# FloppyController.net
KiCad netlist of a schematic drawn in EAGLE
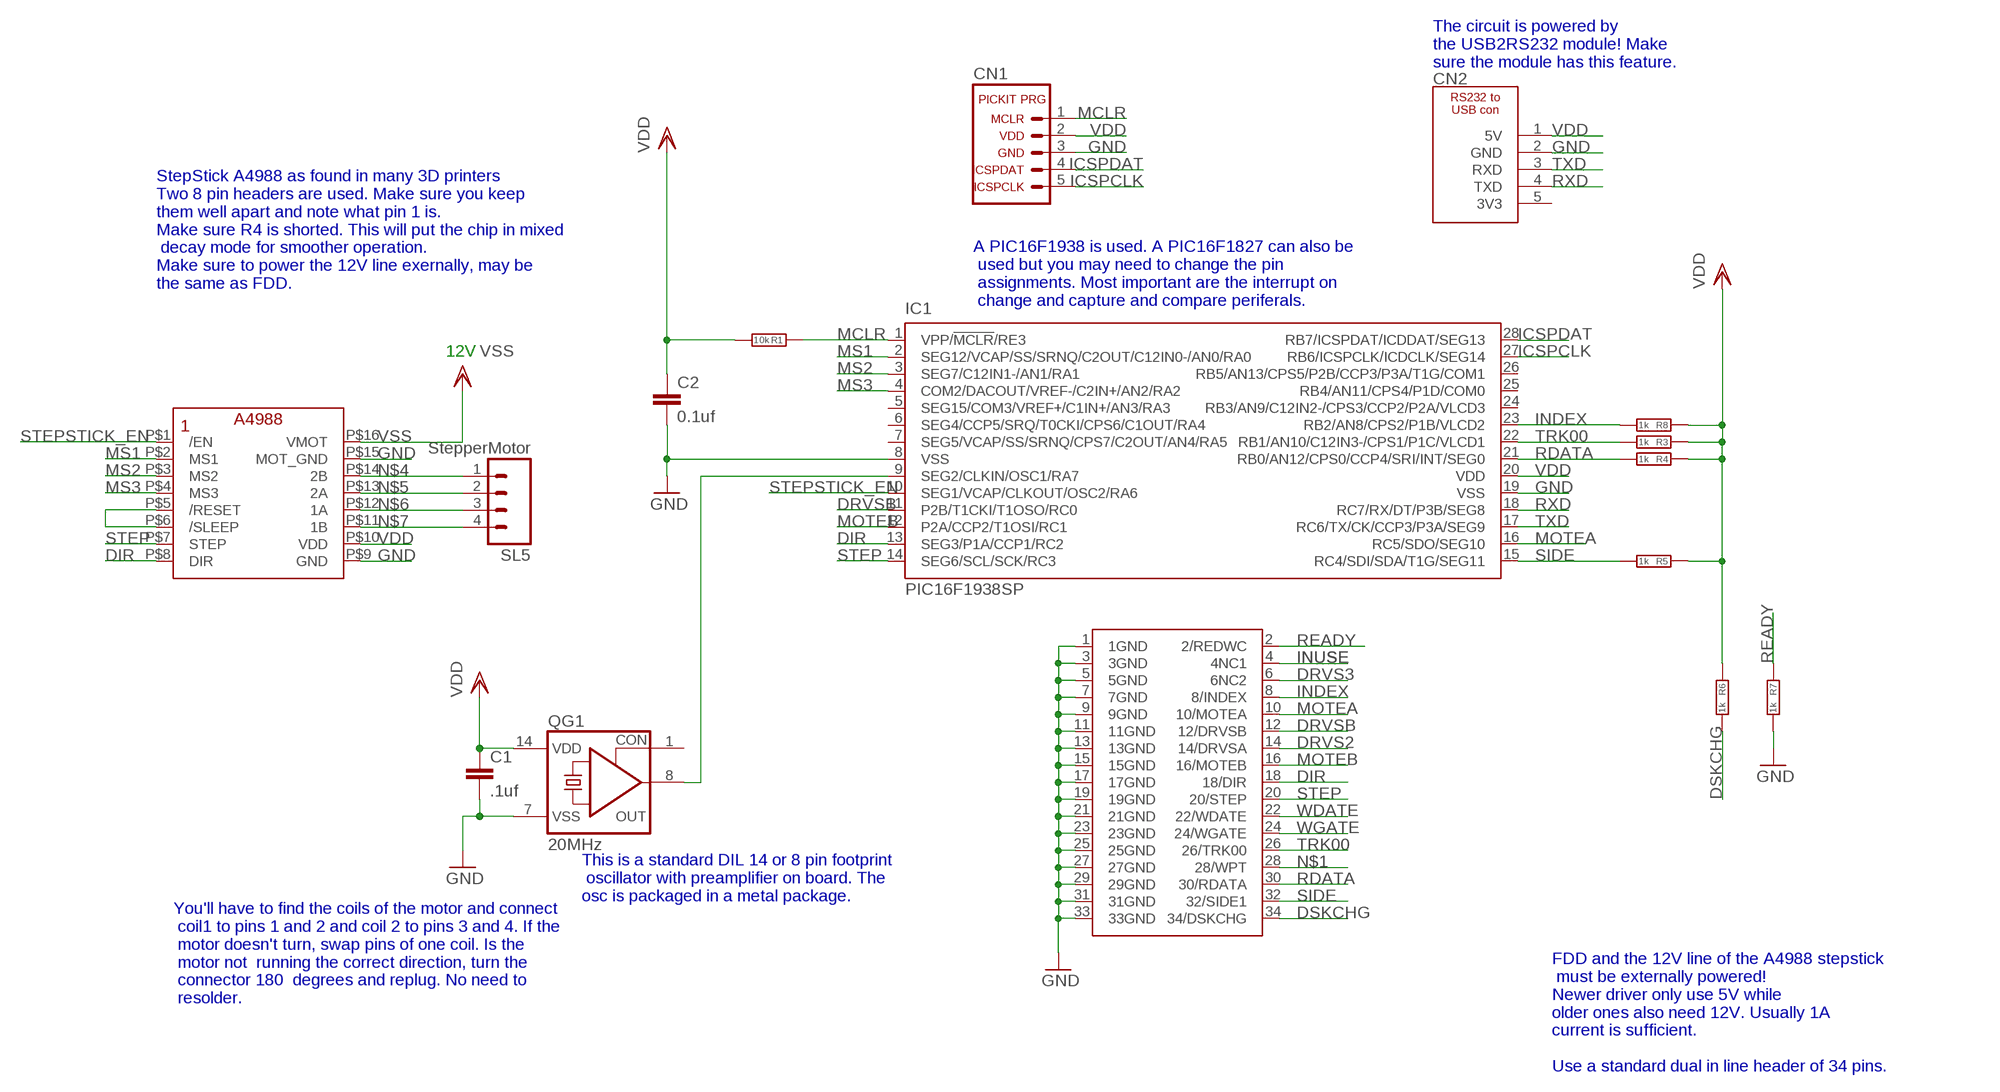
[diagram p0: schematic, sheet 1]

(export (version "E")
  (design (tool "Eeschema 10.0.6"))
  (components
    (comp (ref "C1")
      (value ".1uf")
      (footprint "eagle-import:C5B3")
      (libsource (lib "eagle-import") (part "C5/3"))
    )
    (comp (ref "C2")
      (value "0.1uf")
      (footprint "eagle-import:C5B3")
      (libsource (lib "eagle-import") (part "C5/3"))
    )
    (comp (ref "CN1")
      (value "PICKIT3CONNECTOR")
      (footprint "eagle-import:05P")
      (libsource (lib "eagle-import") (part "PICKIT3CONNECTOR"))
    )
    (comp (ref "CN2")
      (value "RS232_TO_USB_CONNECTOR")
      (footprint "eagle-import:05P")
      (libsource (lib "eagle-import") (part "RS232_TO_USB_CONNECTOR"))
    )
    (comp (ref "IC1")
      (value "PIC16F1938SP")
      (footprint "eagle-import:DIL28-3")
      (fields (field (name "MPN") "PIC16F1938-I/SP"))
      (libsource (lib "eagle-import") (part "PIC16F19SP38"))
    )
    (comp (ref "IC2")
      (value "STEPSTICK_A4988")
      (footprint "eagle-import:STEPSTICK_A4988")
      (libsource (lib "eagle-import") (part "STEPSTICK_A4988"))
    )
    (comp (ref "QG1")
      (value "20MHz")
      (footprint "eagle-import:SG51")
      (libsource (lib "eagle-import") (part "CRYSTAL_RES-SG51"))
    )
    (comp (ref "R1")
      (value "10k")
      (footprint "eagle-import:M1206")
      (libsource (lib "eagle-import") (part "R-EU_M1206"))
    )
    (comp (ref "R3")
      (value "1k")
      (footprint "eagle-import:M1206")
      (libsource (lib "eagle-import") (part "R-EU_M1206"))
    )
    (comp (ref "R4")
      (value "1k")
      (footprint "eagle-import:M1206")
      (libsource (lib "eagle-import") (part "R-EU_M1206"))
    )
    (comp (ref "R5")
      (value "1k")
      (footprint "eagle-import:M1206")
      (libsource (lib "eagle-import") (part "R-EU_M1206"))
    )
    (comp (ref "R6")
      (value "1k")
      (footprint "eagle-import:M1206")
      (libsource (lib "eagle-import") (part "R-EU_M1206"))
    )
    (comp (ref "R7")
      (value "1k")
      (footprint "eagle-import:M1206")
      (libsource (lib "eagle-import") (part "R-EU_M1206"))
    )
    (comp (ref "R8")
      (value "1k")
      (footprint "eagle-import:M1206")
      (libsource (lib "eagle-import") (part "R-EU_M1206"))
    )
    (comp (ref "SL5")
      (value "StepperMotor")
      (footprint "eagle-import:04P")
      (libsource (lib "eagle-import") (part "M04"))
    )
    (comp (ref "U$1")
      (value "FLOPPY_34PIN_CONN")
      (footprint "eagle-import:FLOPPY_34PIN_DUALROW")
      (libsource (lib "eagle-import") (part "FLOPPY_34PIN_CONN"))
    )
  )
  (nets
    (net (code "1") (name "/DIR") (class "Default")
      (node (ref "IC1") (pin "13") (pinfunction "SEG3/P1A/CCP1/RC2_13") (pintype "bidirectional"))
      (node (ref "IC2") (pin "P$8") (pinfunction "DIR_P$8") (pintype "input"))
      (node (ref "U$1") (pin "18") (pinfunction "18/DIR_18") (pintype "input"))
    )
    (net (code "2") (name "/DRVS2") (class "Default")
      (node (ref "U$1") (pin "14") (pinfunction "14/DRVSA_14") (pintype "input"))
    )
    (net (code "3") (name "/DRVS3") (class "Default")
      (node (ref "U$1") (pin "6") (pinfunction "6NC2_6") (pintype "bidirectional"))
    )
    (net (code "4") (name "/DRVSB") (class "Default")
      (node (ref "IC1") (pin "11") (pinfunction "P2B/T1CKI/T1OSO/RC0_11") (pintype "bidirectional"))
      (node (ref "U$1") (pin "12") (pinfunction "12/DRVSB_12") (pintype "input"))
    )
    (net (code "5") (name "/DSKCHG") (class "Default")
      (node (ref "R6") (pin "1") (pinfunction "1_1") (pintype "passive"))
      (node (ref "U$1") (pin "34") (pinfunction "34/DSKCHG_34") (pintype "output"))
    )
    (net (code "6") (name "/ICSPCLK") (class "Default")
      (node (ref "CN1") (pin "5") (pinfunction "5_ICSPCLK_5") (pintype "passive"))
      (node (ref "IC1") (pin "27") (pinfunction "RB6/ICSPCLK/ICDCLK/SEG14_27") (pintype "bidirectional"))
    )
    (net (code "7") (name "/ICSPDAT") (class "Default")
      (node (ref "CN1") (pin "4") (pinfunction "4_ICSPDAT_4") (pintype "passive"))
      (node (ref "IC1") (pin "28") (pinfunction "RB7/ICSPDAT/ICDDAT/SEG13_28") (pintype "bidirectional"))
    )
    (net (code "8") (name "/INDEX") (class "Default")
      (node (ref "IC1") (pin "23") (pinfunction "RB2/AN8/CPS2/P1B/VLCD2_23") (pintype "bidirectional"))
      (node (ref "R8") (pin "1") (pinfunction "1_1") (pintype "passive"))
      (node (ref "U$1") (pin "8") (pinfunction "8/INDEX_8") (pintype "output"))
    )
    (net (code "9") (name "/INUSE") (class "Default")
      (node (ref "U$1") (pin "4") (pinfunction "4NC1_4") (pintype "bidirectional"))
    )
    (net (code "10") (name "/MCLR") (class "Default")
      (node (ref "CN1") (pin "1") (pinfunction "1_MCLR_1") (pintype "passive"))
      (node (ref "IC1") (pin "1") (pinfunction "VPP/~{MCLR}/RE3_1") (pintype "input"))
      (node (ref "R1") (pin "2") (pinfunction "2_2") (pintype "passive"))
    )
    (net (code "11") (name "/MOTEA") (class "Default")
      (node (ref "IC1") (pin "16") (pinfunction "RC5/SDO/SEG10_16") (pintype "bidirectional"))
      (node (ref "U$1") (pin "10") (pinfunction "10/MOTEA_10") (pintype "input"))
    )
    (net (code "12") (name "/MOTEB") (class "Default")
      (node (ref "IC1") (pin "12") (pinfunction "P2A/CCP2/T1OSI/RC1_12") (pintype "bidirectional"))
      (node (ref "U$1") (pin "16") (pinfunction "16/MOTEB_16") (pintype "input"))
    )
    (net (code "13") (name "/MS1") (class "Default")
      (node (ref "IC1") (pin "2") (pinfunction "SEG12/VCAP/SS/SRNQ/C2OUT/C12IN0-/AN0/RA0_2") (pintype "bidirectional"))
      (node (ref "IC2") (pin "P$2") (pinfunction "MS1_P$2") (pintype "input"))
    )
    (net (code "14") (name "/MS2") (class "Default")
      (node (ref "IC1") (pin "3") (pinfunction "SEG7/C12IN1-/AN1/RA1_3") (pintype "bidirectional"))
      (node (ref "IC2") (pin "P$3") (pinfunction "MS2_P$3") (pintype "input"))
    )
    (net (code "15") (name "/MS3") (class "Default")
      (node (ref "IC1") (pin "4") (pinfunction "COM2/DACOUT/VREF-/C2IN+/AN2/RA2_4") (pintype "bidirectional"))
      (node (ref "IC2") (pin "P$4") (pinfunction "MS3_P$4") (pintype "input"))
    )
    (net (code "16") (name "/N$1") (class "Default")
      (node (ref "U$1") (pin "28") (pinfunction "28/WPT_28") (pintype "output"))
    )
    (net (code "17") (name "/N$4") (class "Default")
      (node (ref "IC2") (pin "P$14") (pinfunction "2B_P$14") (pintype "output"))
      (node (ref "SL5") (pin "1") (pinfunction "1_1") (pintype "passive"))
    )
    (net (code "18") (name "/N$5") (class "Default")
      (node (ref "IC2") (pin "P$13") (pinfunction "2A_P$13") (pintype "output"))
      (node (ref "SL5") (pin "2") (pinfunction "2_2") (pintype "passive"))
    )
    (net (code "19") (name "/N$6") (class "Default")
      (node (ref "IC2") (pin "P$12") (pinfunction "1A_P$12") (pintype "output"))
      (node (ref "SL5") (pin "3") (pinfunction "3_3") (pintype "passive"))
    )
    (net (code "20") (name "/N$7") (class "Default")
      (node (ref "IC2") (pin "P$11") (pinfunction "1B_P$11") (pintype "output"))
      (node (ref "SL5") (pin "4") (pinfunction "4_4") (pintype "passive"))
    )
    (net (code "21") (name "/RDATA") (class "Default")
      (node (ref "IC1") (pin "21") (pinfunction "RB0/AN12/CPS0/CCP4/SRI/INT/SEG0_21") (pintype "bidirectional"))
      (node (ref "R4") (pin "1") (pinfunction "1_1") (pintype "passive"))
      (node (ref "U$1") (pin "30") (pinfunction "30/RDATA_30") (pintype "output"))
    )
    (net (code "22") (name "/READY") (class "Default")
      (node (ref "R7") (pin "2") (pinfunction "2_2") (pintype "passive"))
      (node (ref "U$1") (pin "2") (pinfunction "2/REDWC_2") (pintype "input"))
    )
    (net (code "23") (name "/RXD") (class "Default")
      (node (ref "CN2") (pin "4") (pinfunction "TXD_4") (pintype "bidirectional"))
      (node (ref "IC1") (pin "18") (pinfunction "RC7/RX/DT/P3B/SEG8_18") (pintype "bidirectional"))
    )
    (net (code "24") (name "/SIDE") (class "Default")
      (node (ref "IC1") (pin "15") (pinfunction "RC4/SDI/SDA/T1G/SEG11_15") (pintype "bidirectional"))
      (node (ref "R5") (pin "1") (pinfunction "1_1") (pintype "passive"))
      (node (ref "U$1") (pin "32") (pinfunction "32/SIDE1_32") (pintype "input"))
    )
    (net (code "25") (name "/STEP") (class "Default")
      (node (ref "IC1") (pin "14") (pinfunction "SEG6/SCL/SCK/RC3_14") (pintype "bidirectional"))
      (node (ref "IC2") (pin "P$7") (pinfunction "STEP_P$7") (pintype "input"))
      (node (ref "U$1") (pin "20") (pinfunction "20/STEP_20") (pintype "input"))
    )
    (net (code "26") (name "/STEPSTICK_EN") (class "Default")
      (node (ref "IC1") (pin "10") (pinfunction "SEG1/VCAP/CLKOUT/OSC2/RA6_10") (pintype "bidirectional"))
      (node (ref "IC2") (pin "P$1") (pinfunction "/EN_P$1") (pintype "input"))
    )
    (net (code "27") (name "/TRK00") (class "Default")
      (node (ref "IC1") (pin "22") (pinfunction "RB1/AN10/C12IN3-/CPS1/P1C/VLCD1_22") (pintype "bidirectional"))
      (node (ref "R3") (pin "1") (pinfunction "1_1") (pintype "passive"))
      (node (ref "U$1") (pin "26") (pinfunction "26/TRK00_26") (pintype "output"))
    )
    (net (code "28") (name "/TXD") (class "Default")
      (node (ref "CN2") (pin "3") (pinfunction "RXD_3") (pintype "bidirectional"))
      (node (ref "IC1") (pin "17") (pinfunction "RC6/TX/CK/CCP3/P3A/SEG9_17") (pintype "bidirectional"))
    )
    (net (code "29") (name "/WDATE") (class "Default")
      (node (ref "U$1") (pin "22") (pinfunction "22/WDATE_22") (pintype "input"))
    )
    (net (code "30") (name "/WGATE") (class "Default")
      (node (ref "U$1") (pin "24") (pinfunction "24/WGATE_24") (pintype "input"))
    )
    (net (code "31") (name "GND") (class "Default")
      (node (ref "C1") (pin "2") (pinfunction "2_2") (pintype "passive"))
      (node (ref "C2") (pin "2") (pinfunction "2_2") (pintype "passive"))
      (node (ref "CN1") (pin "3") (pinfunction "3_GND_3") (pintype "passive"))
      (node (ref "CN2") (pin "2") (pinfunction "GND_2") (pintype "bidirectional"))
      (node (ref "IC1") (pin "19") (pinfunction "VSS_19") (pintype "power_in"))
      (node (ref "IC1") (pin "8") (pinfunction "VSS_8") (pintype "power_in"))
      (node (ref "IC2") (pin "P$15") (pinfunction "MOT_GND_P$15") (pintype "power_in"))
      (node (ref "IC2") (pin "P$9") (pinfunction "GND_P$9") (pintype "power_in"))
      (node (ref "QG1") (pin "7") (pinfunction "VSS_7") (pintype "power_in"))
      (node (ref "R7") (pin "1") (pinfunction "1_1") (pintype "passive"))
      (node (ref "U$1") (pin "1") (pinfunction "1GND_1") (pintype "power_in"))
      (node (ref "U$1") (pin "11") (pinfunction "11GND_11") (pintype "power_in"))
      (node (ref "U$1") (pin "13") (pinfunction "13GND_13") (pintype "power_in"))
      (node (ref "U$1") (pin "15") (pinfunction "15GND_15") (pintype "power_in"))
      (node (ref "U$1") (pin "17") (pinfunction "17GND_17") (pintype "power_in"))
      (node (ref "U$1") (pin "19") (pinfunction "19GND_19") (pintype "power_in"))
      (node (ref "U$1") (pin "21") (pinfunction "21GND_21") (pintype "power_in"))
      (node (ref "U$1") (pin "23") (pinfunction "23GND_23") (pintype "power_in"))
      (node (ref "U$1") (pin "25") (pinfunction "25GND_25") (pintype "power_in"))
      (node (ref "U$1") (pin "27") (pinfunction "27GND_27") (pintype "power_in"))
      (node (ref "U$1") (pin "29") (pinfunction "29GND_29") (pintype "power_in"))
      (node (ref "U$1") (pin "3") (pinfunction "3GND_3") (pintype "power_in"))
      (node (ref "U$1") (pin "31") (pinfunction "31GND_31") (pintype "power_in"))
      (node (ref "U$1") (pin "33") (pinfunction "33GND_33") (pintype "power_in"))
      (node (ref "U$1") (pin "5") (pinfunction "5GND_5") (pintype "power_in"))
      (node (ref "U$1") (pin "7") (pinfunction "7GND_7") (pintype "power_in"))
      (node (ref "U$1") (pin "9") (pinfunction "9GND_9") (pintype "power_in"))
    )
    (net (code "32") (name "Net-(IC1-SEG2{slash}CLKIN{slash}OSC1{slash}RA7)") (class "Default")
      (node (ref "IC1") (pin "9") (pinfunction "SEG2/CLKIN/OSC1/RA7_9") (pintype "bidirectional"))
      (node (ref "QG1") (pin "8") (pinfunction "OUT_8") (pintype "output"))
    )
    (net (code "33") (name "Net-(IC2-{slash}RESET)") (class "Default")
      (node (ref "IC2") (pin "P$5") (pinfunction "/RESET_P$5") (pintype "input"))
      (node (ref "IC2") (pin "P$6") (pinfunction "/SLEEP_P$6") (pintype "input"))
    )
    (net (code "34") (name "VDD") (class "Default")
      (node (ref "C1") (pin "1") (pinfunction "1_1") (pintype "passive"))
      (node (ref "C2") (pin "1") (pinfunction "1_1") (pintype "passive"))
      (node (ref "CN1") (pin "2") (pinfunction "2_VDD_2") (pintype "passive"))
      (node (ref "CN2") (pin "1") (pinfunction "5V_1") (pintype "bidirectional"))
      (node (ref "IC1") (pin "20") (pinfunction "VDD_20") (pintype "power_in"))
      (node (ref "IC2") (pin "P$10") (pinfunction "VDD_P$10") (pintype "power_in"))
      (node (ref "QG1") (pin "14") (pinfunction "VDD_14") (pintype "power_in"))
      (node (ref "R1") (pin "1") (pinfunction "1_1") (pintype "passive"))
      (node (ref "R3") (pin "2") (pinfunction "2_2") (pintype "passive"))
      (node (ref "R4") (pin "2") (pinfunction "2_2") (pintype "passive"))
      (node (ref "R5") (pin "2") (pinfunction "2_2") (pintype "passive"))
      (node (ref "R6") (pin "2") (pinfunction "2_2") (pintype "passive"))
      (node (ref "R8") (pin "2") (pinfunction "2_2") (pintype "passive"))
    )
    (net (code "35") (name "VSS") (class "Default")
      (node (ref "IC2") (pin "P$16") (pinfunction "VMOT_P$16") (pintype "power_in"))
    )
    (net (code "36") (name "unconnected-(CN2-3V3-Pad5)") (class "Default")
      (node (ref "CN2") (pin "5") (pinfunction "3V3_5") (pintype "bidirectional"))
    )
    (net (code "37") (name "unconnected-(IC1-RB3{slash}AN9{slash}C12IN2-{slash}CPS3{slash}CCP2{slash}P2A{slash}VLCD3-Pad24)") (class "Default")
      (node (ref "IC1") (pin "24") (pinfunction "RB3/AN9/C12IN2-/CPS3/CCP2/P2A/VLCD3_24") (pintype "bidirectional"))
    )
    (net (code "38") (name "unconnected-(IC1-RB4{slash}AN11{slash}CPS4{slash}P1D{slash}COM0-Pad25)") (class "Default")
      (node (ref "IC1") (pin "25") (pinfunction "RB4/AN11/CPS4/P1D/COM0_25") (pintype "bidirectional"))
    )
    (net (code "39") (name "unconnected-(IC1-RB5{slash}AN13{slash}CPS5{slash}P2B{slash}CCP3{slash}P3A{slash}T1G{slash}COM1-Pad26)") (class "Default")
      (node (ref "IC1") (pin "26") (pinfunction "RB5/AN13/CPS5/P2B/CCP3/P3A/T1G/COM1_26") (pintype "bidirectional"))
    )
    (net (code "40") (name "unconnected-(IC1-SEG4{slash}CCP5{slash}SRQ{slash}T0CKI{slash}CPS6{slash}C1OUT{slash}RA4-Pad6)") (class "Default")
      (node (ref "IC1") (pin "6") (pinfunction "SEG4/CCP5/SRQ/T0CKI/CPS6/C1OUT/RA4_6") (pintype "bidirectional"))
    )
    (net (code "41") (name "unconnected-(IC1-SEG5{slash}VCAP{slash}SS{slash}SRNQ{slash}CPS7{slash}C2OUT{slash}AN4{slash}RA5-Pad7)") (class "Default")
      (node (ref "IC1") (pin "7") (pinfunction "SEG5/VCAP/SS/SRNQ/CPS7/C2OUT/AN4/RA5_7") (pintype "bidirectional"))
    )
    (net (code "42") (name "unconnected-(IC1-SEG15{slash}COM3{slash}VREF+{slash}C1IN+{slash}AN3{slash}RA3-Pad5)") (class "Default")
      (node (ref "IC1") (pin "5") (pinfunction "SEG15/COM3/VREF+/C1IN+/AN3/RA3_5") (pintype "bidirectional"))
    )
    (net (code "43") (name "unconnected-(QG1-CON-Pad1)") (class "Default")
      (node (ref "QG1") (pin "1") (pinfunction "CON_1") (pintype "input"))
    )
  )
)
